# eeprom.net
KiCad netlist of a schematic drawn in Altium Designer
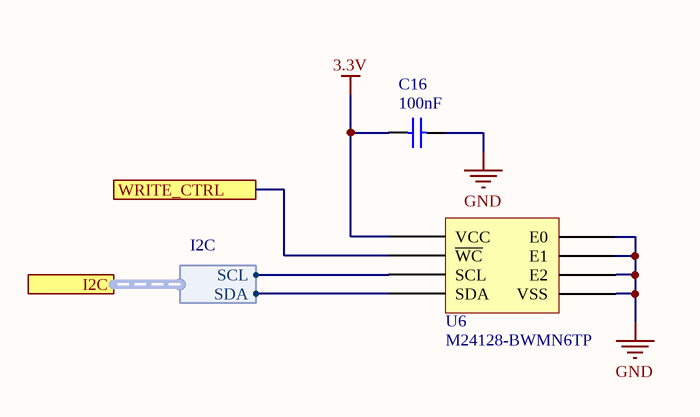
[diagram p0: eeprom.SchDoc]

(export (version "E")
  (design (tool "Eeschema 10.0.6"))
  (components
    (comp (ref "C16")
      (value "100nF")
      (footprint "0603 - Capacitor")
      (description "Nonpolarized Capacitor")
      (fields (field (name "Comment") "Capacitor - Nonpolarized"))
      (libsource (lib "General") (part "Capacitor - Nonpolarized"))
    )
    (comp (ref "U6")
      (value "~")
      (footprint "SOIC127P600X175-8N")
      (description "EEPROM Memory IC 128Kb (16K x 8) I²C 1 MHz 450 ns 8-SOIC")
      (fields (field (name "MANUFACTURER_PART_NUMBER") "M24128-BWMN6TP"))
      (libsource (lib "General") (part "M24128-BWMN6TP"))
    )
  )
  (nets
    (net (code "2") (name "/SCL") (class "Default")
      (node (ref "U6") (pin "6") (pinfunction "SCL_6") (pintype "passive"))
    )
    (net (code "3") (name "/SDA") (class "Default")
      (node (ref "U6") (pin "5") (pinfunction "SDA_5") (pintype "passive"))
    )
    (net (code "4") (name "/WRITE_CTRL") (class "Default")
      (node (ref "U6") (pin "7") (pinfunction "~{WC}_7") (pintype "passive"))
    )
    (net (code "6") (name "3.3V") (class "Default")
      (node (ref "C16") (pin "1") (pinfunction "1_1") (pintype "passive"))
      (node (ref "U6") (pin "8") (pinfunction "VCC_8") (pintype "passive"))
    )
    (net (code "7") (name "GND") (class "Default")
      (node (ref "C16") (pin "2") (pinfunction "2_2") (pintype "passive"))
      (node (ref "U6") (pin "1") (pinfunction "E0_1") (pintype "passive"))
      (node (ref "U6") (pin "2") (pinfunction "E1_2") (pintype "passive"))
      (node (ref "U6") (pin "3") (pinfunction "E2_3") (pintype "passive"))
      (node (ref "U6") (pin "4") (pinfunction "VSS_4") (pintype "passive"))
    )
  )
)
